# Esquematico_Deck_-_Crazyflie.net
KiCad netlist of a schematic drawn in Altium Designer
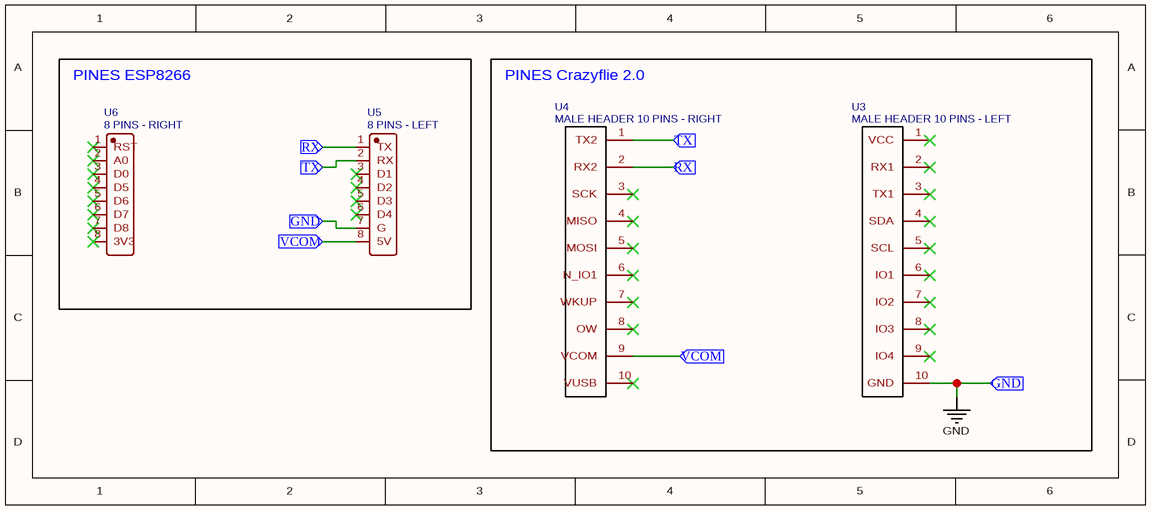
[diagram p0: Esquematico Deck - Crazyflie.schdoc]

(export (version "E")
  (design (tool "Eeschema 10.0.6"))
  (components
    (comp (ref "U3")
      (value "MALE HEADER 10 PINS - LEFT")
      (fields (field (name "CONTRIBUTOR") "gor18062"))
      (libsource (lib "altium-import") (part "root_0_MALE HEADER 10 PINS - LEFT_"))
    )
    (comp (ref "U4")
      (value "MALE HEADER 10 PINS - RIGHT")
      (fields (field (name "CONTRIBUTOR") "gor18062"))
      (libsource (lib "altium-import") (part "root_0_MALE HEADER 10 PINS - RIGHT_"))
    )
    (comp (ref "U5")
      (value "8 PINS - LEFT")
      (fields
        (field (name "BOM_SUPPLIER PART") "C2935979")
        (field (name "BOM_MANUFACTURER PART") "DM254R-11-08-85")
        (field (name "CONTRIBUTOR") "LCSC")
      )
      (libsource (lib "altium-import") (part "root_0_8 PINS - LEFT_"))
    )
    (comp (ref "U6")
      (value "8 PINS - RIGHT")
      (fields
        (field (name "BOM_SUPPLIER PART") "C2935979")
        (field (name "BOM_MANUFACTURER PART") "DM254R-11-08-85")
        (field (name "CONTRIBUTOR") "LCSC")
      )
      (libsource (lib "altium-import") (part "root_0_8 PINS - RIGHT_"))
    )
  )
  (nets
    (net (code "1") (name "/RX") (class "Default")
      (node (ref "U4") (pin "2") (pinfunction "RX2_2") (pintype "passive"))
      (node (ref "U5") (pin "1") (pinfunction "TX_1") (pintype "passive"))
    )
    (net (code "2") (name "/TX") (class "Default")
      (node (ref "U4") (pin "1") (pinfunction "TX2_1") (pintype "passive"))
      (node (ref "U5") (pin "2") (pinfunction "RX_2") (pintype "passive"))
    )
    (net (code "3") (name "/VCOM") (class "Default")
      (node (ref "U4") (pin "9") (pinfunction "VCOM_9") (pintype "passive"))
      (node (ref "U5") (pin "8") (pinfunction "5V_8") (pintype "passive"))
    )
    (net (code "4") (name "GND") (class "Default")
      (node (ref "U3") (pin "10") (pinfunction "GND_10") (pintype "passive"))
      (node (ref "U5") (pin "7") (pinfunction "G_7") (pintype "passive"))
    )
    (net (code "5") (name "unconnected-(U3-IO1-Pad6)") (class "Default")
      (node (ref "U3") (pin "6") (pinfunction "IO1_6") (pintype "passive+no_connect"))
    )
    (net (code "6") (name "unconnected-(U3-IO2-Pad7)") (class "Default")
      (node (ref "U3") (pin "7") (pinfunction "IO2_7") (pintype "passive+no_connect"))
    )
    (net (code "7") (name "unconnected-(U3-IO3-Pad8)") (class "Default")
      (node (ref "U3") (pin "8") (pinfunction "IO3_8") (pintype "passive+no_connect"))
    )
    (net (code "8") (name "unconnected-(U3-IO4-Pad9)") (class "Default")
      (node (ref "U3") (pin "9") (pinfunction "IO4_9") (pintype "passive+no_connect"))
    )
    (net (code "9") (name "unconnected-(U3-RX1-Pad2)") (class "Default")
      (node (ref "U3") (pin "2") (pinfunction "RX1_2") (pintype "passive+no_connect"))
    )
    (net (code "10") (name "unconnected-(U3-SCL-Pad5)") (class "Default")
      (node (ref "U3") (pin "5") (pinfunction "SCL_5") (pintype "passive+no_connect"))
    )
    (net (code "11") (name "unconnected-(U3-SDA-Pad4)") (class "Default")
      (node (ref "U3") (pin "4") (pinfunction "SDA_4") (pintype "passive+no_connect"))
    )
    (net (code "12") (name "unconnected-(U3-TX1-Pad3)") (class "Default")
      (node (ref "U3") (pin "3") (pinfunction "TX1_3") (pintype "passive+no_connect"))
    )
    (net (code "13") (name "unconnected-(U3-VCC-Pad1)") (class "Default")
      (node (ref "U3") (pin "1") (pinfunction "VCC_1") (pintype "passive+no_connect"))
    )
    (net (code "14") (name "unconnected-(U4-MISO-Pad4)") (class "Default")
      (node (ref "U4") (pin "4") (pinfunction "MISO_4") (pintype "passive+no_connect"))
    )
    (net (code "15") (name "unconnected-(U4-MOSI-Pad5)") (class "Default")
      (node (ref "U4") (pin "5") (pinfunction "MOSI_5") (pintype "passive+no_connect"))
    )
    (net (code "16") (name "unconnected-(U4-N_IO1-Pad6)") (class "Default")
      (node (ref "U4") (pin "6") (pinfunction "N_IO1_6") (pintype "passive+no_connect"))
    )
    (net (code "17") (name "unconnected-(U4-OW-Pad8)") (class "Default")
      (node (ref "U4") (pin "8") (pinfunction "OW_8") (pintype "passive+no_connect"))
    )
    (net (code "18") (name "unconnected-(U4-SCK-Pad3)") (class "Default")
      (node (ref "U4") (pin "3") (pinfunction "SCK_3") (pintype "passive+no_connect"))
    )
    (net (code "19") (name "unconnected-(U4-VUSB-Pad10)") (class "Default")
      (node (ref "U4") (pin "10") (pinfunction "VUSB_10") (pintype "passive+no_connect"))
    )
    (net (code "20") (name "unconnected-(U4-WKUP-Pad7)") (class "Default")
      (node (ref "U4") (pin "7") (pinfunction "WKUP_7") (pintype "passive+no_connect"))
    )
    (net (code "21") (name "unconnected-(U5-D1-Pad3)") (class "Default")
      (node (ref "U5") (pin "3") (pinfunction "D1_3") (pintype "passive+no_connect"))
    )
    (net (code "22") (name "unconnected-(U5-D2-Pad4)") (class "Default")
      (node (ref "U5") (pin "4") (pinfunction "D2_4") (pintype "passive+no_connect"))
    )
    (net (code "23") (name "unconnected-(U5-D3-Pad5)") (class "Default")
      (node (ref "U5") (pin "5") (pinfunction "D3_5") (pintype "passive+no_connect"))
    )
    (net (code "24") (name "unconnected-(U5-D4-Pad6)") (class "Default")
      (node (ref "U5") (pin "6") (pinfunction "D4_6") (pintype "passive+no_connect"))
    )
    (net (code "25") (name "unconnected-(U6-3V3-Pad8)") (class "Default")
      (node (ref "U6") (pin "8") (pinfunction "3V3_8") (pintype "passive+no_connect"))
    )
    (net (code "26") (name "unconnected-(U6-A0-Pad2)") (class "Default")
      (node (ref "U6") (pin "2") (pinfunction "A0_2") (pintype "passive+no_connect"))
    )
    (net (code "27") (name "unconnected-(U6-D0-Pad3)") (class "Default")
      (node (ref "U6") (pin "3") (pinfunction "D0_3") (pintype "passive+no_connect"))
    )
    (net (code "28") (name "unconnected-(U6-D5-Pad4)") (class "Default")
      (node (ref "U6") (pin "4") (pinfunction "D5_4") (pintype "passive+no_connect"))
    )
    (net (code "29") (name "unconnected-(U6-D6-Pad5)") (class "Default")
      (node (ref "U6") (pin "5") (pinfunction "D6_5") (pintype "passive+no_connect"))
    )
    (net (code "30") (name "unconnected-(U6-D7-Pad6)") (class "Default")
      (node (ref "U6") (pin "6") (pinfunction "D7_6") (pintype "passive+no_connect"))
    )
    (net (code "31") (name "unconnected-(U6-D8-Pad7)") (class "Default")
      (node (ref "U6") (pin "7") (pinfunction "D8_7") (pintype "passive+no_connect"))
    )
    (net (code "32") (name "unconnected-(U6-RST-Pad1)") (class "Default")
      (node (ref "U6") (pin "1") (pinfunction "RST_1") (pintype "passive+no_connect"))
    )
  )
)
